# unicorder-mk-2_0.net
KiCad netlist of a schematic drawn in EAGLE
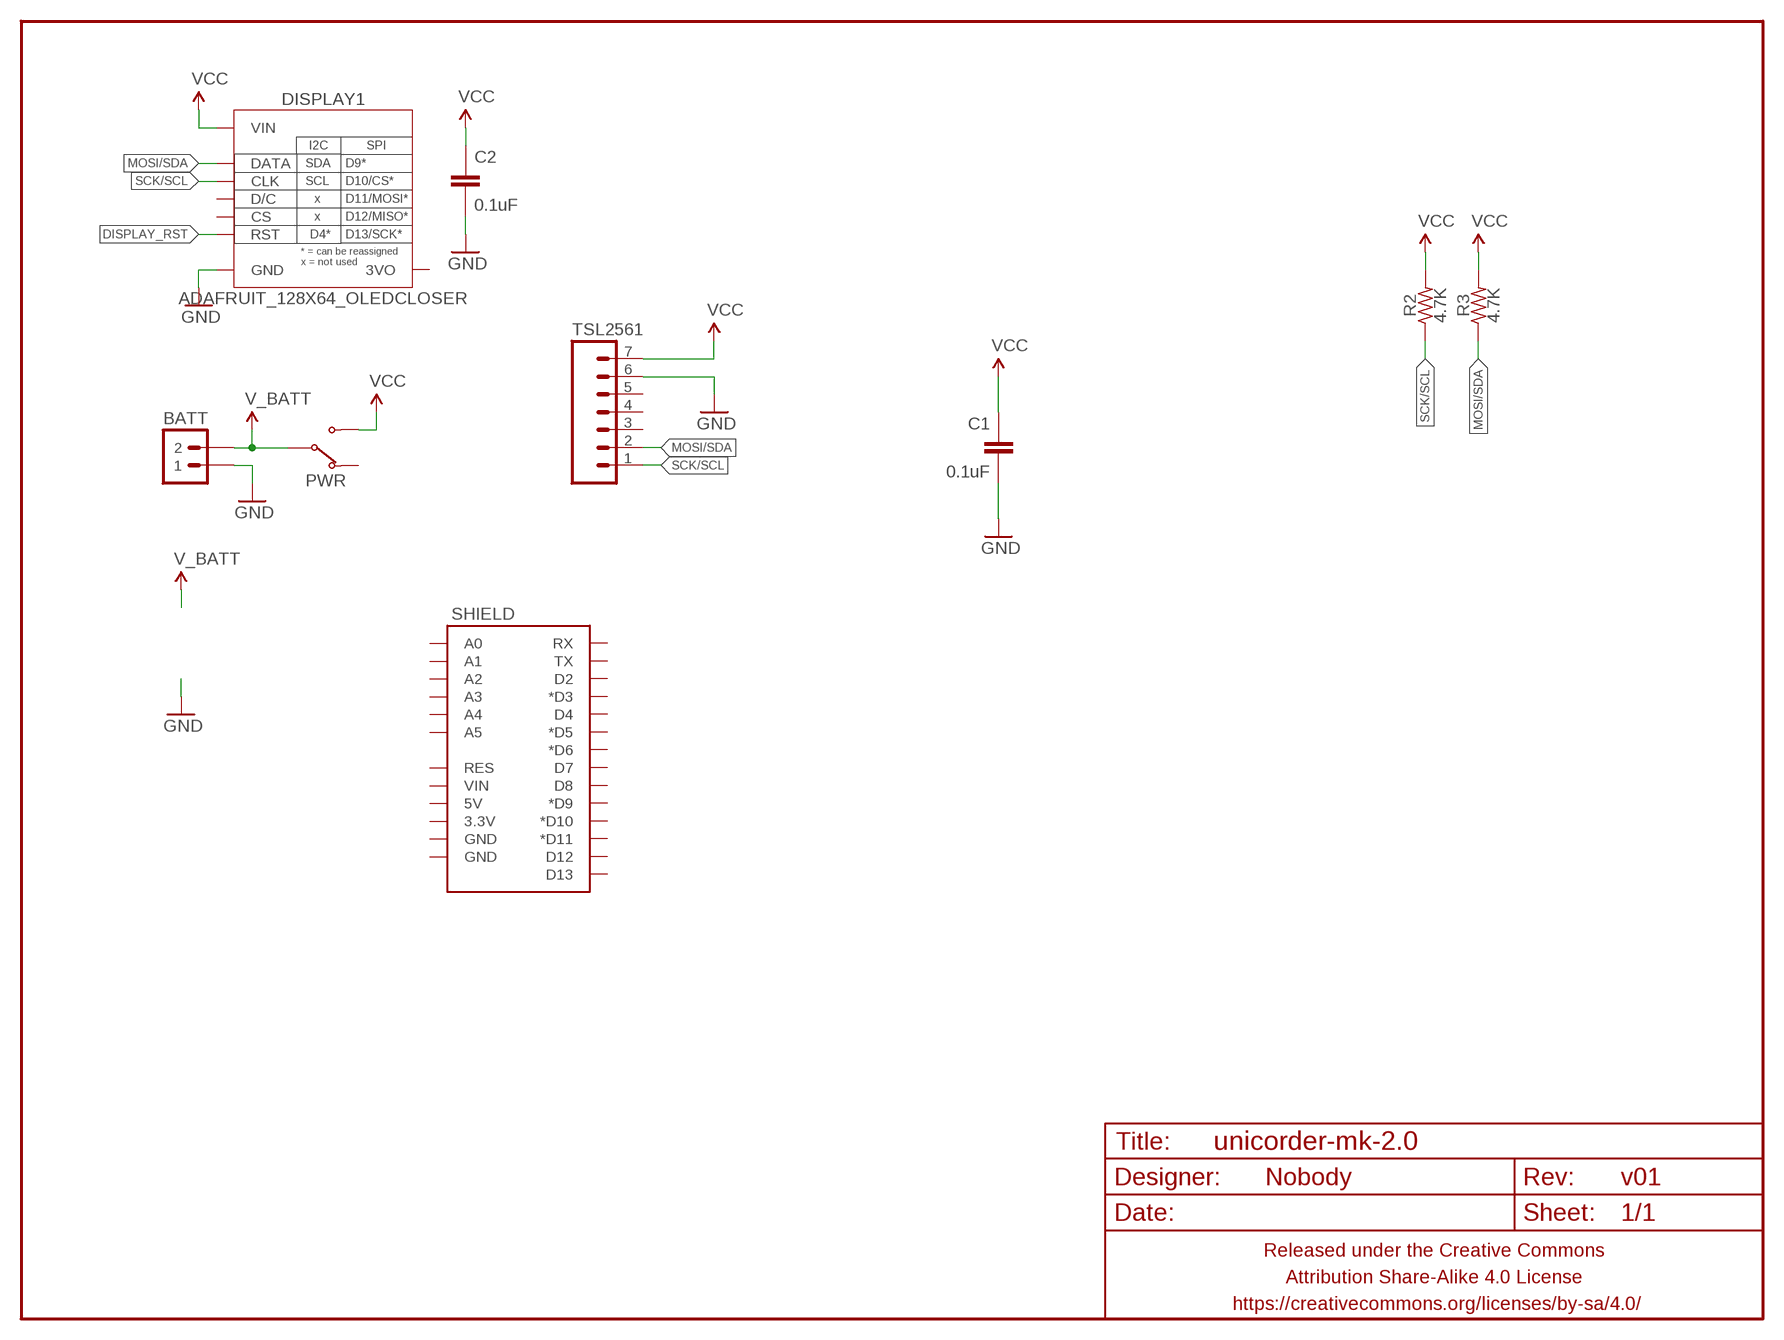
[diagram p0: schematic, sheet 1]

(export (version "E")
  (design (tool "Eeschema 10.0.6"))
  (components
    (comp (ref "BATT")
      (value "M02JST-PTH-VERT")
      (footprint "eagle-import:JST-2-PH-VERT-PTH")
      (libsource (lib "eagle-import") (part "M02JST-PTH-VERT"))
    )
    (comp (ref "C1")
      (value "0.1uF")
      (footprint "eagle-import:C025-024X044")
      (libsource (lib "eagle-import") (part "CAPACITOR-CERAMIC025-024X044"))
    )
    (comp (ref "C2")
      (value "0.1uF")
      (footprint "eagle-import:C025-024X044")
      (libsource (lib "eagle-import") (part "CAPACITOR-CERAMIC025-024X044"))
    )
    (comp (ref "DISPLAY1")
      (value "ADAFRUIT_128X64_OLEDCLOSER")
      (footprint "eagle-import:ADAFRUIT_128X64_OLED_CLOSER")
      (libsource (lib "eagle-import") (part "ADAFRUIT_128X64_OLEDCLOSER"))
    )
    (comp (ref "FRAME1")
      (value "FRAME-LETTERNO_PACKAGE")
      (footprint "eagle-import:DUMMY")
      (fields (field (name "DESIGNER") "Nobody"))
      (libsource (lib "eagle-import") (part "FRAME-LETTERNO_PACKAGE"))
    )
    (comp (ref "PWR")
      (value "SWITCH-SPDTPTH-RA-2MM")
      (footprint "eagle-import:SPDT-RA-2MM")
      (libsource (lib "eagle-import") (part "SWITCH-SPDTPTH-RA-2MM"))
    )
    (comp (ref "R2")
      (value "4.7K")
      (footprint "eagle-import:RESISTOR-AXIAL-PTH-5.08MM")
      (libsource (lib "eagle-import") (part "RESISTORPTH-AXIAL-5.08MM"))
    )
    (comp (ref "R3")
      (value "4.7K")
      (footprint "eagle-import:RESISTOR-AXIAL-PTH-5.08MM")
      (libsource (lib "eagle-import") (part "RESISTORPTH-AXIAL-5.08MM"))
    )
    (comp (ref "SHIELD")
      (value "ARDUINO_SHIELD_SMALLER")
      (footprint "eagle-import:ARDUINO_SHIELD_NOOUTLINE_INSIDE_SMALLER")
      (libsource (lib "eagle-import") (part "ARDUINO_SHIELD_SMALLER"))
    )
    (comp (ref "TSL2561")
      (value "M07PTH-SLIMASS")
      (footprint "eagle-import:1X07_PTH_SLIMASS")
      (libsource (lib "eagle-import") (part "M07PTH-SLIMASS"))
    )
  )
  (nets
    (net (code "1") (name "DISPLAY_RST") (class "Default")
      (node (ref "DISPLAY1") (pin "RST") (pinfunction "RST_RST") (pintype "bidirectional"))
    )
    (net (code "2") (name "GND") (class "Default")
      (node (ref "BATT") (pin "1") (pinfunction "1_1") (pintype "passive"))
      (node (ref "C1") (pin "2") (pinfunction "2_2") (pintype "passive"))
      (node (ref "C2") (pin "2") (pinfunction "2_2") (pintype "passive"))
      (node (ref "DISPLAY1") (pin "GND") (pinfunction "GND_GND") (pintype "bidirectional"))
      (node (ref "TSL2561") (pin "6") (pinfunction "6_6") (pintype "passive"))
    )
    (net (code "3") (name "MOSI{slash}SDA") (class "Default")
      (node (ref "DISPLAY1") (pin "DATA") (pinfunction "DATA_DATA") (pintype "bidirectional"))
      (node (ref "R3") (pin "P$1") (pinfunction "1_P$1") (pintype "passive"))
      (node (ref "TSL2561") (pin "2") (pinfunction "2_2") (pintype "passive"))
    )
    (net (code "4") (name "SCK{slash}SCL") (class "Default")
      (node (ref "DISPLAY1") (pin "CLK") (pinfunction "CLK_CLK") (pintype "bidirectional"))
      (node (ref "R2") (pin "P$1") (pinfunction "1_P$1") (pintype "passive"))
      (node (ref "TSL2561") (pin "1") (pinfunction "1_1") (pintype "passive"))
    )
    (net (code "5") (name "VCC") (class "Default")
      (node (ref "C1") (pin "1") (pinfunction "1_1") (pintype "passive"))
      (node (ref "C2") (pin "1") (pinfunction "1_1") (pintype "passive"))
      (node (ref "DISPLAY1") (pin "VIN") (pinfunction "VIN_VIN") (pintype "bidirectional"))
      (node (ref "PWR") (pin "3") (pinfunction "NO_3") (pintype "passive"))
      (node (ref "R2") (pin "P$2") (pinfunction "2_P$2") (pintype "passive"))
      (node (ref "R3") (pin "P$2") (pinfunction "2_P$2") (pintype "passive"))
      (node (ref "TSL2561") (pin "7") (pinfunction "7_7") (pintype "passive"))
    )
    (net (code "6") (name "V_BATT") (class "Default")
      (node (ref "BATT") (pin "2") (pinfunction "2_2") (pintype "passive"))
      (node (ref "PWR") (pin "2") (pinfunction "COM_2") (pintype "passive"))
    )
    (net (code "7") (name "unconnected-(DISPLAY1-Pad3VO)") (class "Default")
      (node (ref "DISPLAY1") (pin "3VO") (pinfunction "3VO_3VO") (pintype "bidirectional"))
    )
    (net (code "8") (name "unconnected-(DISPLAY1-PadCS)") (class "Default")
      (node (ref "DISPLAY1") (pin "CS") (pinfunction "CS_CS") (pintype "bidirectional"))
    )
    (net (code "9") (name "unconnected-(DISPLAY1-PadD{slash}C)") (class "Default")
      (node (ref "DISPLAY1") (pin "D/C") (pinfunction "D/C_D/C") (pintype "bidirectional"))
    )
    (net (code "10") (name "unconnected-(PWR-NC-Pad1)") (class "Default")
      (node (ref "PWR") (pin "1") (pinfunction "NC_1") (pintype "passive"))
    )
    (net (code "11") (name "unconnected-(SHIELD-*D3-PadD3)") (class "Default")
      (node (ref "SHIELD") (pin "D3") (pinfunction "*D3_D3") (pintype "bidirectional"))
    )
    (net (code "12") (name "unconnected-(SHIELD-*D5-PadD5)") (class "Default")
      (node (ref "SHIELD") (pin "D5") (pinfunction "*D5_D5") (pintype "bidirectional"))
    )
    (net (code "13") (name "unconnected-(SHIELD-*D6-PadD6)") (class "Default")
      (node (ref "SHIELD") (pin "D6") (pinfunction "*D6_D6") (pintype "bidirectional"))
    )
    (net (code "14") (name "unconnected-(SHIELD-*D9-PadD9)") (class "Default")
      (node (ref "SHIELD") (pin "D9") (pinfunction "*D9_D9") (pintype "bidirectional"))
    )
    (net (code "15") (name "unconnected-(SHIELD-*D10-PadD10)") (class "Default")
      (node (ref "SHIELD") (pin "D10") (pinfunction "*D10_D10") (pintype "bidirectional"))
    )
    (net (code "16") (name "unconnected-(SHIELD-*D11-PadD11)") (class "Default")
      (node (ref "SHIELD") (pin "D11") (pinfunction "*D11_D11") (pintype "bidirectional"))
    )
    (net (code "17") (name "unconnected-(SHIELD-GND-PadGND@0)") (class "Default")
      (node (ref "SHIELD") (pin "GND@0") (pinfunction "GND_GND@0") (pintype "bidirectional"))
    )
    (net (code "18") (name "unconnected-(SHIELD-GND-PadGND@1)") (class "Default")
      (node (ref "SHIELD") (pin "GND@1") (pinfunction "GND_GND@1") (pintype "bidirectional"))
    )
    (net (code "19") (name "unconnected-(SHIELD-Pad3.3V)") (class "Default")
      (node (ref "SHIELD") (pin "3.3V") (pinfunction "3.3V_3.3V") (pintype "bidirectional"))
    )
    (net (code "20") (name "unconnected-(SHIELD-Pad5V)") (class "Default")
      (node (ref "SHIELD") (pin "5V") (pinfunction "5V_5V") (pintype "bidirectional"))
    )
    (net (code "21") (name "unconnected-(SHIELD-PadA0)") (class "Default")
      (node (ref "SHIELD") (pin "A0") (pinfunction "A0_A0") (pintype "bidirectional"))
    )
    (net (code "22") (name "unconnected-(SHIELD-PadA1)") (class "Default")
      (node (ref "SHIELD") (pin "A1") (pinfunction "A1_A1") (pintype "bidirectional"))
    )
    (net (code "23") (name "unconnected-(SHIELD-PadA2)") (class "Default")
      (node (ref "SHIELD") (pin "A2") (pinfunction "A2_A2") (pintype "bidirectional"))
    )
    (net (code "24") (name "unconnected-(SHIELD-PadA3)") (class "Default")
      (node (ref "SHIELD") (pin "A3") (pinfunction "A3_A3") (pintype "bidirectional"))
    )
    (net (code "25") (name "unconnected-(SHIELD-PadA4)") (class "Default")
      (node (ref "SHIELD") (pin "A4") (pinfunction "A4_A4") (pintype "bidirectional"))
    )
    (net (code "26") (name "unconnected-(SHIELD-PadA5)") (class "Default")
      (node (ref "SHIELD") (pin "A5") (pinfunction "A5_A5") (pintype "bidirectional"))
    )
    (net (code "27") (name "unconnected-(SHIELD-PadD2)") (class "Default")
      (node (ref "SHIELD") (pin "D2") (pinfunction "D2_D2") (pintype "bidirectional"))
    )
    (net (code "28") (name "unconnected-(SHIELD-PadD4)") (class "Default")
      (node (ref "SHIELD") (pin "D4") (pinfunction "D4_D4") (pintype "bidirectional"))
    )
    (net (code "29") (name "unconnected-(SHIELD-PadD7)") (class "Default")
      (node (ref "SHIELD") (pin "D7") (pinfunction "D7_D7") (pintype "bidirectional"))
    )
    (net (code "30") (name "unconnected-(SHIELD-PadD8)") (class "Default")
      (node (ref "SHIELD") (pin "D8") (pinfunction "D8_D8") (pintype "bidirectional"))
    )
    (net (code "31") (name "unconnected-(SHIELD-PadD12)") (class "Default")
      (node (ref "SHIELD") (pin "D12") (pinfunction "D12_D12") (pintype "bidirectional"))
    )
    (net (code "32") (name "unconnected-(SHIELD-PadD13)") (class "Default")
      (node (ref "SHIELD") (pin "D13") (pinfunction "D13_D13") (pintype "bidirectional"))
    )
    (net (code "33") (name "unconnected-(SHIELD-PadRES)") (class "Default")
      (node (ref "SHIELD") (pin "RES") (pinfunction "RES_RES") (pintype "bidirectional"))
    )
    (net (code "34") (name "unconnected-(SHIELD-PadRX)") (class "Default")
      (node (ref "SHIELD") (pin "RX") (pinfunction "RX_RX") (pintype "bidirectional"))
    )
    (net (code "35") (name "unconnected-(SHIELD-PadTX)") (class "Default")
      (node (ref "SHIELD") (pin "TX") (pinfunction "TX_TX") (pintype "bidirectional"))
    )
    (net (code "36") (name "unconnected-(SHIELD-PadVIN)") (class "Default")
      (node (ref "SHIELD") (pin "VIN") (pinfunction "VIN_VIN") (pintype "bidirectional"))
    )
    (net (code "37") (name "unconnected-(TSL2561-Pad3)") (class "Default")
      (node (ref "TSL2561") (pin "3") (pinfunction "3_3") (pintype "passive"))
    )
    (net (code "38") (name "unconnected-(TSL2561-Pad4)") (class "Default")
      (node (ref "TSL2561") (pin "4") (pinfunction "4_4") (pintype "passive"))
    )
    (net (code "39") (name "unconnected-(TSL2561-Pad5)") (class "Default")
      (node (ref "TSL2561") (pin "5") (pinfunction "5_5") (pintype "passive"))
    )
  )
)
